# SHT20.net
KiCad netlist of a schematic drawn in Altium Designer
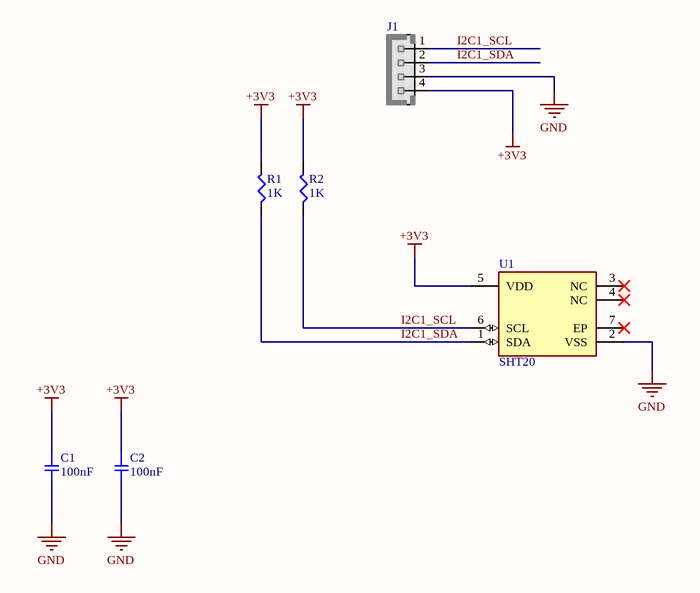
[diagram p0: SHT20.SchDoc]

(export (version "E")
  (design (tool "Eeschema 10.0.6"))
  (components
    (comp (ref "C1")
      (value "100nF")
      (footprint "SMD-0805C")
      (description "CAP CER 100nF 50V X7R 0805")
      (fields
        (field (name "DIGI-KEY PART NUMBER") "490-13986-1-ND")
        (field (name "PART NUMBER") "GC321AD72E103KX01D")
      )
      (libsource (lib "capacitor_murata_0805") (part "GC321AD72E103KX01D"))
    )
    (comp (ref "C2")
      (value "100nF")
      (footprint "SMD-0805C")
      (description "CAP CER 100nF 50V X7R 0805")
      (fields
        (field (name "DIGI-KEY PART NUMBER") "490-13986-1-ND")
        (field (name "PART NUMBER") "GC321AD72E103KX01D")
      )
      (libsource (lib "capacitor_murata_0805") (part "GC321AD72E103KX01D"))
    )
    (comp (ref "J1")
      (value "SHT20 Mod")
      (footprint "XH_4")
      (description "JST-XH pitch: 2.5mm")
      (libsource (lib "chila ") (part "XH_4"))
    )
    (comp (ref "R1")
      (value "1K")
      (footprint "SMD-0805-RES")
      (description "1KΩ 0805")
      (fields (field (name "PART NUMBER") "ERJ-6BQF1R0V") (field (name "DIGI-KEY PART NUMBER") "P17499CT-ND"))
      (libsource (lib "Panasonic_ERJ_0805") (part "ERJ-6BQF1R0V"))
    )
    (comp (ref "R2")
      (value "1K")
      (footprint "SMD-0805-RES")
      (description "1KΩ 0805")
      (fields (field (name "PART NUMBER") "ERJ-6BQF1R0V") (field (name "DIGI-KEY PART NUMBER") "P17499CT-ND"))
      (libsource (lib "Panasonic_ERJ_0805") (part "ERJ-6BQF1R0V"))
    )
    (comp (ref "U1")
      (value "SHT20")
      (footprint "FP-SHT20-MFG")
      (description "SENSOR HUMID/TEMP 3V I2C 3% SMD")
      (fields
        (field (name "OCTOPART") "https://octopart.com/sht20-sensirion-47077745")
        (field (name "MANUFACTURER") "Sensirion")
      )
      (libsource (lib "Altium Content Vault") (part "5058aba635ec8ccb61858bacc329a36"))
    )
  )
  (nets
    (net (code "1") (name "+3V3") (class "Default")
      (node (ref "C1") (pin "1") (pinfunction "1_1") (pintype "passive"))
      (node (ref "C2") (pin "1") (pinfunction "1_1") (pintype "passive"))
      (node (ref "J1") (pin "4") (pinfunction "4_4") (pintype "passive"))
      (node (ref "R1") (pin "2") (pinfunction "2_2") (pintype "passive"))
      (node (ref "R2") (pin "2") (pinfunction "2_2") (pintype "passive"))
      (node (ref "U1") (pin "5") (pinfunction "VDD_5") (pintype "power_in"))
    )
    (net (code "2") (name "/I2C1_SCL") (class "Default")
      (node (ref "J1") (pin "1") (pinfunction "1_1") (pintype "passive"))
      (node (ref "R2") (pin "1") (pinfunction "1_1") (pintype "passive"))
      (node (ref "U1") (pin "6") (pinfunction "SCL_6") (pintype "bidirectional"))
    )
    (net (code "3") (name "/I2C1_SDA") (class "Default")
      (node (ref "J1") (pin "2") (pinfunction "2_2") (pintype "passive"))
      (node (ref "R1") (pin "1") (pinfunction "1_1") (pintype "passive"))
      (node (ref "U1") (pin "1") (pinfunction "SDA_1") (pintype "bidirectional"))
    )
    (net (code "4") (name "GND") (class "Default")
      (node (ref "C1") (pin "2") (pinfunction "2_2") (pintype "passive"))
      (node (ref "C2") (pin "2") (pinfunction "2_2") (pintype "passive"))
      (node (ref "J1") (pin "3") (pinfunction "3_3") (pintype "passive"))
      (node (ref "U1") (pin "2") (pinfunction "VSS_2") (pintype "power_in"))
    )
    (net (code "5") (name "unconnected-(U1-EP-Pad7)") (class "Default")
      (node (ref "U1") (pin "7") (pinfunction "EP_7") (pintype "power_in+no_connect"))
    )
    (net (code "6") (name "unconnected-(U1-NC-Pad3)") (class "Default")
      (node (ref "U1") (pin "3") (pinfunction "NC_3") (pintype "passive+no_connect"))
    )
    (net (code "7") (name "unconnected-(U1-NC-Pad4)") (class "Default")
      (node (ref "U1") (pin "4") (pinfunction "NC_4") (pintype "passive+no_connect"))
    )
  )
)
